# tape_rewinder.net
KiCad netlist of a schematic drawn in Altium Designer
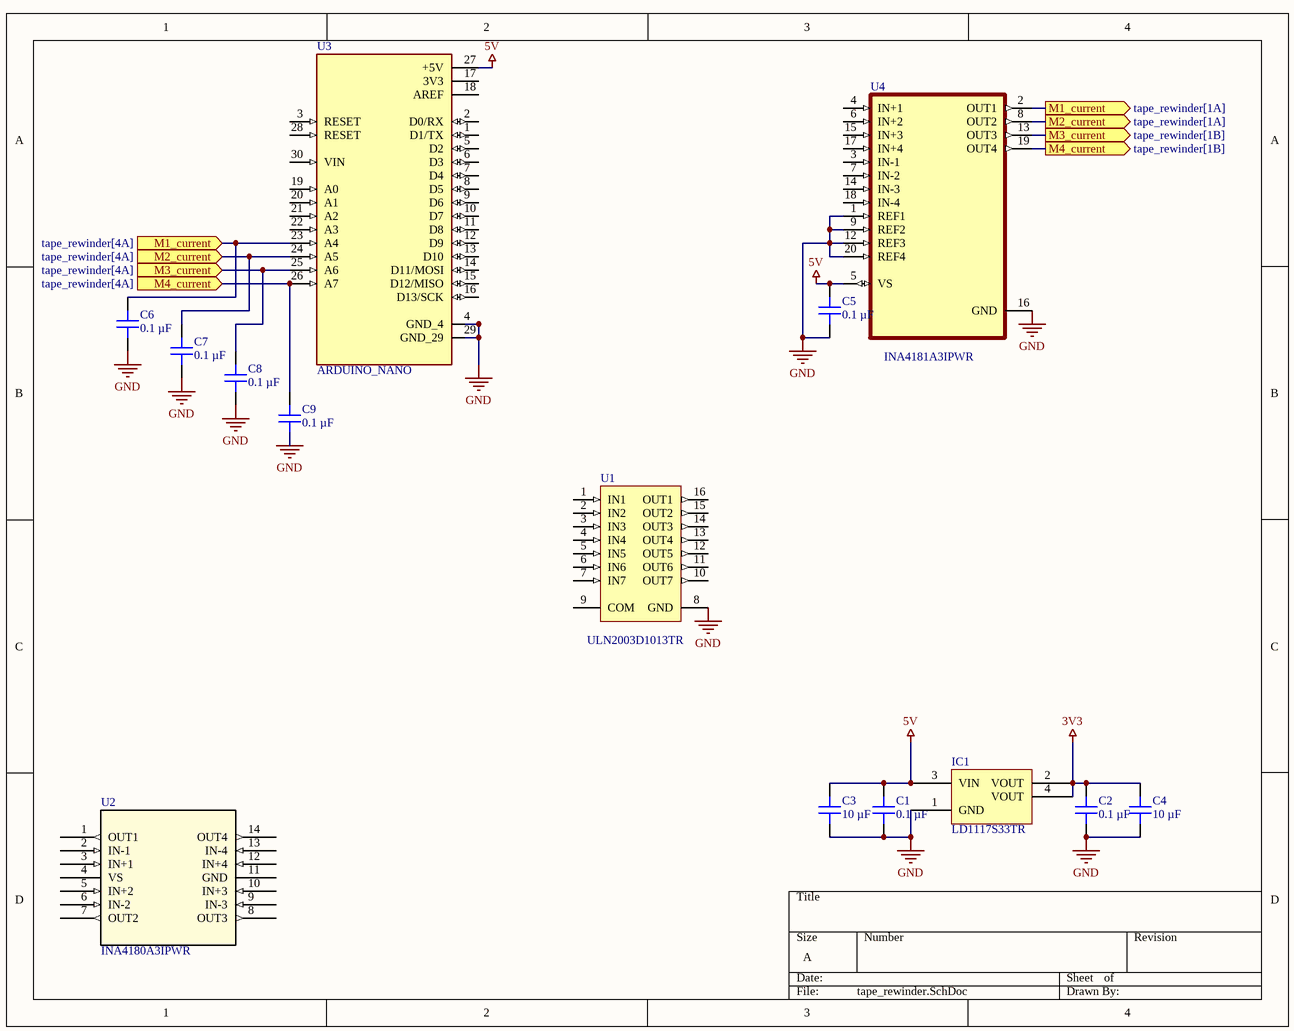
[diagram p0: tape_rewinder.SchDoc]

(export (version "E")
  (design (tool "Eeschema 10.0.6"))
  (components
    (comp (ref "C1")
      (value "0.1 µF")
      (footprint "CAP 0805_2012")
      (description "CAP CER 0.1UF 50V X7R 0805")
      (fields
        (field (name "PART NUMBER") "CC0805MRX7R9BB104")
        (field (name "CAPACITANCE") "0.1 µF")
        (field (name "MANUFACTURER") "Yageo")
      )
      (libsource (lib "Celestial Altium Library - altium_library") (part "Capacitor"))
    )
    (comp (ref "C2")
      (value "0.1 µF")
      (footprint "CAP 0805_2012")
      (description "CAP CER 0.1UF 50V X7R 0805")
      (fields
        (field (name "PART NUMBER") "CC0805MRX7R9BB104")
        (field (name "CAPACITANCE") "0.1 µF")
        (field (name "MANUFACTURER") "Yageo")
      )
      (libsource (lib "Celestial Altium Library - altium_library") (part "Capacitor"))
    )
    (comp (ref "C3")
      (value "10 µF")
      (footprint "CAP 0805_2012")
      (description "CAP CER 10UF 16V X7R 0805")
      (fields
        (field (name "PART NUMBER") "CC0805MKX7R7BB106")
        (field (name "CAPACITANCE") "10 µF")
        (field (name "MANUFACTURER") "Yageo")
      )
      (libsource (lib "Celestial Altium Library - altium_library") (part "Capacitor"))
    )
    (comp (ref "C4")
      (value "10 µF")
      (footprint "CAP 0805_2012")
      (description "CAP CER 10UF 16V X7R 0805")
      (fields
        (field (name "PART NUMBER") "CC0805MKX7R7BB106")
        (field (name "CAPACITANCE") "10 µF")
        (field (name "MANUFACTURER") "Yageo")
      )
      (libsource (lib "Celestial Altium Library - altium_library") (part "Capacitor"))
    )
    (comp (ref "C5")
      (value "0.1 µF")
      (footprint "CAP 0805_2012")
      (description "CAP CER 0.1UF 50V X7R 0805")
      (fields
        (field (name "PART NUMBER") "CC0805MRX7R9BB104")
        (field (name "CAPACITANCE") "0.1 µF")
        (field (name "MANUFACTURER") "Yageo")
      )
      (libsource (lib "Celestial Altium Library - altium_library") (part "Capacitor"))
    )
    (comp (ref "C6")
      (value "0.1 µF")
      (footprint "CAP 0805_2012")
      (description "CAP CER 0.1UF 50V X7R 0805")
      (fields
        (field (name "PART NUMBER") "CC0805MRX7R9BB104")
        (field (name "CAPACITANCE") "0.1 µF")
        (field (name "MANUFACTURER") "Yageo")
      )
      (libsource (lib "Celestial Altium Library - altium_library") (part "Capacitor"))
    )
    (comp (ref "C7")
      (value "0.1 µF")
      (footprint "CAP 0805_2012")
      (description "CAP CER 0.1UF 50V X7R 0805")
      (fields
        (field (name "PART NUMBER") "CC0805MRX7R9BB104")
        (field (name "CAPACITANCE") "0.1 µF")
        (field (name "MANUFACTURER") "Yageo")
      )
      (libsource (lib "Celestial Altium Library - altium_library") (part "Capacitor"))
    )
    (comp (ref "C8")
      (value "0.1 µF")
      (footprint "CAP 0805_2012")
      (description "CAP CER 0.1UF 50V X7R 0805")
      (fields
        (field (name "PART NUMBER") "CC0805MRX7R9BB104")
        (field (name "CAPACITANCE") "0.1 µF")
        (field (name "MANUFACTURER") "Yageo")
      )
      (libsource (lib "Celestial Altium Library - altium_library") (part "Capacitor"))
    )
    (comp (ref "C9")
      (value "0.1 µF")
      (footprint "CAP 0805_2012")
      (description "CAP CER 0.1UF 50V X7R 0805")
      (fields
        (field (name "PART NUMBER") "CC0805MRX7R9BB104")
        (field (name "CAPACITANCE") "0.1 µF")
        (field (name "MANUFACTURER") "Yageo")
      )
      (libsource (lib "Celestial Altium Library - altium_library") (part "Capacitor"))
    )
    (comp (ref "IC1")
      (value "LD1117S33TR")
      (footprint "ST SOT-223")
      (description "IC REG LINEAR 3.3V 800MA SOT223")
      (fields (field (name "MANUFACTURER") "STMicroelectronics"))
      (libsource (lib "Celestial Altium Library - altium_library") (part "ST LD1117"))
    )
    (comp (ref "U1")
      (value "ULN2003D1013TR")
      (footprint "STM-SO-16_M")
      (fields (field (name "MANUFACTURER") "STMicroelectronics"))
      (libsource (lib "Altium Content Vault") (part "STM-ULN2003A-PDIP-16"))
    )
    (comp (ref "U2")
      (value "INA4180A3IPWR")
      (footprint "*SOP65P640X120-14N")
      (description "26V, quad channel, 350kHz current sense amplifier 14-TSSOP -40 to 125")
      (fields (field (name "COPYRIGHT") "Copyright (C) 2025 Ultra Librarian. All rights reserved."))
      (libsource (lib "INA4180A3IPWR") (part "INA4180A3IPWR"))
    )
    (comp (ref "U3")
      (value "ARDUINO_NANO")
      (footprint "MODULE_ARDUINO_NANO")
      (description "Small, complete, and breadboard-friendly board based on the ATmega328 (Arduino Nano 3.x)")
      (fields (field (name "MF") "Arduino") (field (name "MP") "Arduino Nano"))
      (libsource (lib "ARDUINO_NANO") (part "ARDUINO_NANO"))
    )
    (comp (ref "U4")
      (value "INA4181A3IPWR")
      (footprint "SOP65P640X120-20N")
      (libsource (lib "INA4181A3IPWR") (part "INA4181A3IPWR"))
    )
  )
  (nets
    (net (code "1") (name "/M1_current") (class "Default")
      (node (ref "C6") (pin "2") (pinfunction "2_2") (pintype "passive"))
      (node (ref "U3") (pin "23") (pinfunction "A4_23") (pintype "input"))
      (node (ref "U4") (pin "2") (pinfunction "OUT1_2") (pintype "output"))
    )
    (net (code "2") (name "/M2_current") (class "Default")
      (node (ref "C7") (pin "2") (pinfunction "2_2") (pintype "passive"))
      (node (ref "U3") (pin "24") (pinfunction "A5_24") (pintype "input"))
      (node (ref "U4") (pin "8") (pinfunction "OUT2_8") (pintype "output"))
    )
    (net (code "3") (name "/M3_current") (class "Default")
      (node (ref "C8") (pin "2") (pinfunction "2_2") (pintype "passive"))
      (node (ref "U3") (pin "25") (pinfunction "A6_25") (pintype "input"))
      (node (ref "U4") (pin "13") (pinfunction "OUT3_13") (pintype "output"))
    )
    (net (code "4") (name "/M4_current") (class "Default")
      (node (ref "C9") (pin "2") (pinfunction "2_2") (pintype "passive"))
      (node (ref "U3") (pin "26") (pinfunction "A7_26") (pintype "input"))
      (node (ref "U4") (pin "19") (pinfunction "OUT4_19") (pintype "output"))
    )
    (net (code "5") (name "3V3") (class "Default")
      (node (ref "C2") (pin "2") (pinfunction "2_2") (pintype "passive"))
      (node (ref "C4") (pin "2") (pinfunction "2_2") (pintype "passive"))
      (node (ref "IC1") (pin "2") (pinfunction "VOUT_2") (pintype "passive"))
      (node (ref "IC1") (pin "4") (pinfunction "VOUT_4") (pintype "passive"))
    )
    (net (code "6") (name "5V") (class "Default")
      (node (ref "C1") (pin "2") (pinfunction "2_2") (pintype "passive"))
      (node (ref "C3") (pin "2") (pinfunction "2_2") (pintype "passive"))
      (node (ref "C5") (pin "2") (pinfunction "2_2") (pintype "passive"))
      (node (ref "IC1") (pin "3") (pinfunction "VIN_3") (pintype "passive"))
      (node (ref "U3") (pin "27") (pinfunction "+5V_27") (pintype "power_in"))
      (node (ref "U4") (pin "5") (pinfunction "VS_5") (pintype "bidirectional"))
    )
    (net (code "7") (name "GND") (class "Default")
      (node (ref "C1") (pin "1") (pinfunction "1_1") (pintype "passive"))
      (node (ref "C2") (pin "1") (pinfunction "1_1") (pintype "passive"))
      (node (ref "C3") (pin "1") (pinfunction "1_1") (pintype "passive"))
      (node (ref "C4") (pin "1") (pinfunction "1_1") (pintype "passive"))
      (node (ref "C5") (pin "1") (pinfunction "1_1") (pintype "passive"))
      (node (ref "C6") (pin "1") (pinfunction "1_1") (pintype "passive"))
      (node (ref "C7") (pin "1") (pinfunction "1_1") (pintype "passive"))
      (node (ref "C8") (pin "1") (pinfunction "1_1") (pintype "passive"))
      (node (ref "C9") (pin "1") (pinfunction "1_1") (pintype "passive"))
      (node (ref "IC1") (pin "1") (pinfunction "GND_1") (pintype "passive"))
      (node (ref "U1") (pin "8") (pinfunction "GND_8") (pintype "power_in"))
      (node (ref "U3") (pin "29") (pinfunction "GND_29_29") (pintype "power_in"))
      (node (ref "U3") (pin "4") (pinfunction "GND_4_4") (pintype "power_in"))
      (node (ref "U4") (pin "1") (pinfunction "REF1_1") (pintype "input"))
      (node (ref "U4") (pin "12") (pinfunction "REF3_12") (pintype "input"))
      (node (ref "U4") (pin "16") (pinfunction "GND_16") (pintype "power_in"))
      (node (ref "U4") (pin "20") (pinfunction "REF4_20") (pintype "input"))
      (node (ref "U4") (pin "9") (pinfunction "REF2_9") (pintype "input"))
    )
    (net (code "8") (name "unconnected-(U1-COM-Pad9)") (class "Default")
      (node (ref "U1") (pin "9") (pinfunction "COM_9") (pintype "passive"))
    )
    (net (code "9") (name "unconnected-(U1-IN1-Pad1)") (class "Default")
      (node (ref "U1") (pin "1") (pinfunction "IN1_1") (pintype "input"))
    )
    (net (code "10") (name "unconnected-(U1-IN2-Pad2)") (class "Default")
      (node (ref "U1") (pin "2") (pinfunction "IN2_2") (pintype "input"))
    )
    (net (code "11") (name "unconnected-(U1-IN3-Pad3)") (class "Default")
      (node (ref "U1") (pin "3") (pinfunction "IN3_3") (pintype "input"))
    )
    (net (code "12") (name "unconnected-(U1-IN4-Pad4)") (class "Default")
      (node (ref "U1") (pin "4") (pinfunction "IN4_4") (pintype "input"))
    )
    (net (code "13") (name "unconnected-(U1-IN5-Pad5)") (class "Default")
      (node (ref "U1") (pin "5") (pinfunction "IN5_5") (pintype "input"))
    )
    (net (code "14") (name "unconnected-(U1-IN6-Pad6)") (class "Default")
      (node (ref "U1") (pin "6") (pinfunction "IN6_6") (pintype "input"))
    )
    (net (code "15") (name "unconnected-(U1-IN7-Pad7)") (class "Default")
      (node (ref "U1") (pin "7") (pinfunction "IN7_7") (pintype "input"))
    )
    (net (code "16") (name "unconnected-(U1-OUT1-Pad16)") (class "Default")
      (node (ref "U1") (pin "16") (pinfunction "OUT1_16") (pintype "output"))
    )
    (net (code "17") (name "unconnected-(U1-OUT2-Pad15)") (class "Default")
      (node (ref "U1") (pin "15") (pinfunction "OUT2_15") (pintype "output"))
    )
    (net (code "18") (name "unconnected-(U1-OUT3-Pad14)") (class "Default")
      (node (ref "U1") (pin "14") (pinfunction "OUT3_14") (pintype "output"))
    )
    (net (code "19") (name "unconnected-(U1-OUT4-Pad13)") (class "Default")
      (node (ref "U1") (pin "13") (pinfunction "OUT4_13") (pintype "output"))
    )
    (net (code "20") (name "unconnected-(U1-OUT5-Pad12)") (class "Default")
      (node (ref "U1") (pin "12") (pinfunction "OUT5_12") (pintype "output"))
    )
    (net (code "21") (name "unconnected-(U1-OUT6-Pad11)") (class "Default")
      (node (ref "U1") (pin "11") (pinfunction "OUT6_11") (pintype "output"))
    )
    (net (code "22") (name "unconnected-(U1-OUT7-Pad10)") (class "Default")
      (node (ref "U1") (pin "10") (pinfunction "OUT7_10") (pintype "output"))
    )
    (net (code "23") (name "unconnected-(U2-GND-Pad11)") (class "Default")
      (node (ref "U2") (pin "11") (pinfunction "GND_11") (pintype "power_in"))
    )
    (net (code "24") (name "unconnected-(U2-IN+1-Pad3)") (class "Default")
      (node (ref "U2") (pin "3") (pinfunction "IN+1_3") (pintype "input"))
    )
    (net (code "25") (name "unconnected-(U2-IN+2-Pad5)") (class "Default")
      (node (ref "U2") (pin "5") (pinfunction "IN+2_5") (pintype "input"))
    )
    (net (code "26") (name "unconnected-(U2-IN+3-Pad10)") (class "Default")
      (node (ref "U2") (pin "10") (pinfunction "IN+3_10") (pintype "input"))
    )
    (net (code "27") (name "unconnected-(U2-IN+4-Pad12)") (class "Default")
      (node (ref "U2") (pin "12") (pinfunction "IN+4_12") (pintype "input"))
    )
    (net (code "28") (name "unconnected-(U2-IN-1-Pad2)") (class "Default")
      (node (ref "U2") (pin "2") (pinfunction "IN-1_2") (pintype "input"))
    )
    (net (code "29") (name "unconnected-(U2-IN-2-Pad6)") (class "Default")
      (node (ref "U2") (pin "6") (pinfunction "IN-2_6") (pintype "input"))
    )
    (net (code "30") (name "unconnected-(U2-IN-3-Pad9)") (class "Default")
      (node (ref "U2") (pin "9") (pinfunction "IN-3_9") (pintype "input"))
    )
    (net (code "31") (name "unconnected-(U2-IN-4-Pad13)") (class "Default")
      (node (ref "U2") (pin "13") (pinfunction "IN-4_13") (pintype "input"))
    )
    (net (code "32") (name "unconnected-(U2-OUT1-Pad1)") (class "Default")
      (node (ref "U2") (pin "1") (pinfunction "OUT1_1") (pintype "output"))
    )
    (net (code "33") (name "unconnected-(U2-OUT2-Pad7)") (class "Default")
      (node (ref "U2") (pin "7") (pinfunction "OUT2_7") (pintype "output"))
    )
    (net (code "34") (name "unconnected-(U2-OUT3-Pad8)") (class "Default")
      (node (ref "U2") (pin "8") (pinfunction "OUT3_8") (pintype "output"))
    )
    (net (code "35") (name "unconnected-(U2-OUT4-Pad14)") (class "Default")
      (node (ref "U2") (pin "14") (pinfunction "OUT4_14") (pintype "output"))
    )
    (net (code "36") (name "unconnected-(U2-VS-Pad4)") (class "Default")
      (node (ref "U2") (pin "4") (pinfunction "VS_4") (pintype "power_in"))
    )
    (net (code "37") (name "unconnected-(U3-3V3-Pad17)") (class "Default")
      (node (ref "U3") (pin "17") (pinfunction "3V3_17") (pintype "power_in"))
    )
    (net (code "38") (name "unconnected-(U3-A0-Pad19)") (class "Default")
      (node (ref "U3") (pin "19") (pinfunction "A0_19") (pintype "input"))
    )
    (net (code "39") (name "unconnected-(U3-A1-Pad20)") (class "Default")
      (node (ref "U3") (pin "20") (pinfunction "A1_20") (pintype "input"))
    )
    (net (code "40") (name "unconnected-(U3-A2-Pad21)") (class "Default")
      (node (ref "U3") (pin "21") (pinfunction "A2_21") (pintype "input"))
    )
    (net (code "41") (name "unconnected-(U3-A3-Pad22)") (class "Default")
      (node (ref "U3") (pin "22") (pinfunction "A3_22") (pintype "input"))
    )
    (net (code "42") (name "unconnected-(U3-AREF-Pad18)") (class "Default")
      (node (ref "U3") (pin "18") (pinfunction "AREF_18") (pintype "power_in"))
    )
    (net (code "43") (name "unconnected-(U3-D0{slash}RX-Pad2)") (class "Default")
      (node (ref "U3") (pin "2") (pinfunction "D0/RX_2") (pintype "bidirectional"))
    )
    (net (code "44") (name "unconnected-(U3-D1{slash}TX-Pad1)") (class "Default")
      (node (ref "U3") (pin "1") (pinfunction "D1/TX_1") (pintype "bidirectional"))
    )
    (net (code "45") (name "unconnected-(U3-D2-Pad5)") (class "Default")
      (node (ref "U3") (pin "5") (pinfunction "D2_5") (pintype "bidirectional"))
    )
    (net (code "46") (name "unconnected-(U3-D3-Pad6)") (class "Default")
      (node (ref "U3") (pin "6") (pinfunction "D3_6") (pintype "bidirectional"))
    )
    (net (code "47") (name "unconnected-(U3-D4-Pad7)") (class "Default")
      (node (ref "U3") (pin "7") (pinfunction "D4_7") (pintype "bidirectional"))
    )
    (net (code "48") (name "unconnected-(U3-D5-Pad8)") (class "Default")
      (node (ref "U3") (pin "8") (pinfunction "D5_8") (pintype "bidirectional"))
    )
    (net (code "49") (name "unconnected-(U3-D6-Pad9)") (class "Default")
      (node (ref "U3") (pin "9") (pinfunction "D6_9") (pintype "bidirectional"))
    )
    (net (code "50") (name "unconnected-(U3-D7-Pad10)") (class "Default")
      (node (ref "U3") (pin "10") (pinfunction "D7_10") (pintype "bidirectional"))
    )
    (net (code "51") (name "unconnected-(U3-D8-Pad11)") (class "Default")
      (node (ref "U3") (pin "11") (pinfunction "D8_11") (pintype "bidirectional"))
    )
    (net (code "52") (name "unconnected-(U3-D9-Pad12)") (class "Default")
      (node (ref "U3") (pin "12") (pinfunction "D9_12") (pintype "bidirectional"))
    )
    (net (code "53") (name "unconnected-(U3-D10-Pad13)") (class "Default")
      (node (ref "U3") (pin "13") (pinfunction "D10_13") (pintype "bidirectional"))
    )
    (net (code "54") (name "unconnected-(U3-D11{slash}MOSI-Pad14)") (class "Default")
      (node (ref "U3") (pin "14") (pinfunction "D11/MOSI_14") (pintype "bidirectional"))
    )
    (net (code "55") (name "unconnected-(U3-D12{slash}MISO-Pad15)") (class "Default")
      (node (ref "U3") (pin "15") (pinfunction "D12/MISO_15") (pintype "bidirectional"))
    )
    (net (code "56") (name "unconnected-(U3-D13{slash}SCK-Pad16)") (class "Default")
      (node (ref "U3") (pin "16") (pinfunction "D13/SCK_16") (pintype "bidirectional"))
    )
    (net (code "57") (name "unconnected-(U3-RESET-Pad3)") (class "Default")
      (node (ref "U3") (pin "3") (pinfunction "RESET_3") (pintype "input"))
    )
    (net (code "58") (name "unconnected-(U3-RESET-Pad28)") (class "Default")
      (node (ref "U3") (pin "28") (pinfunction "RESET_28") (pintype "input"))
    )
    (net (code "59") (name "unconnected-(U3-VIN-Pad30)") (class "Default")
      (node (ref "U3") (pin "30") (pinfunction "VIN_30") (pintype "input"))
    )
    (net (code "60") (name "unconnected-(U4-IN+1-Pad4)") (class "Default")
      (node (ref "U4") (pin "4") (pinfunction "IN+1_4") (pintype "input"))
    )
    (net (code "61") (name "unconnected-(U4-IN+2-Pad6)") (class "Default")
      (node (ref "U4") (pin "6") (pinfunction "IN+2_6") (pintype "input"))
    )
    (net (code "62") (name "unconnected-(U4-IN+3-Pad15)") (class "Default")
      (node (ref "U4") (pin "15") (pinfunction "IN+3_15") (pintype "input"))
    )
    (net (code "63") (name "unconnected-(U4-IN+4-Pad17)") (class "Default")
      (node (ref "U4") (pin "17") (pinfunction "IN+4_17") (pintype "input"))
    )
    (net (code "64") (name "unconnected-(U4-IN-1-Pad3)") (class "Default")
      (node (ref "U4") (pin "3") (pinfunction "IN-1_3") (pintype "input"))
    )
    (net (code "65") (name "unconnected-(U4-IN-2-Pad7)") (class "Default")
      (node (ref "U4") (pin "7") (pinfunction "IN-2_7") (pintype "input"))
    )
    (net (code "66") (name "unconnected-(U4-IN-3-Pad14)") (class "Default")
      (node (ref "U4") (pin "14") (pinfunction "IN-3_14") (pintype "input"))
    )
    (net (code "67") (name "unconnected-(U4-IN-4-Pad18)") (class "Default")
      (node (ref "U4") (pin "18") (pinfunction "IN-4_18") (pintype "input"))
    )
  )
)
